# St_Olavs_Alarm.net
KiCad netlist of a schematic drawn in Altium Designer
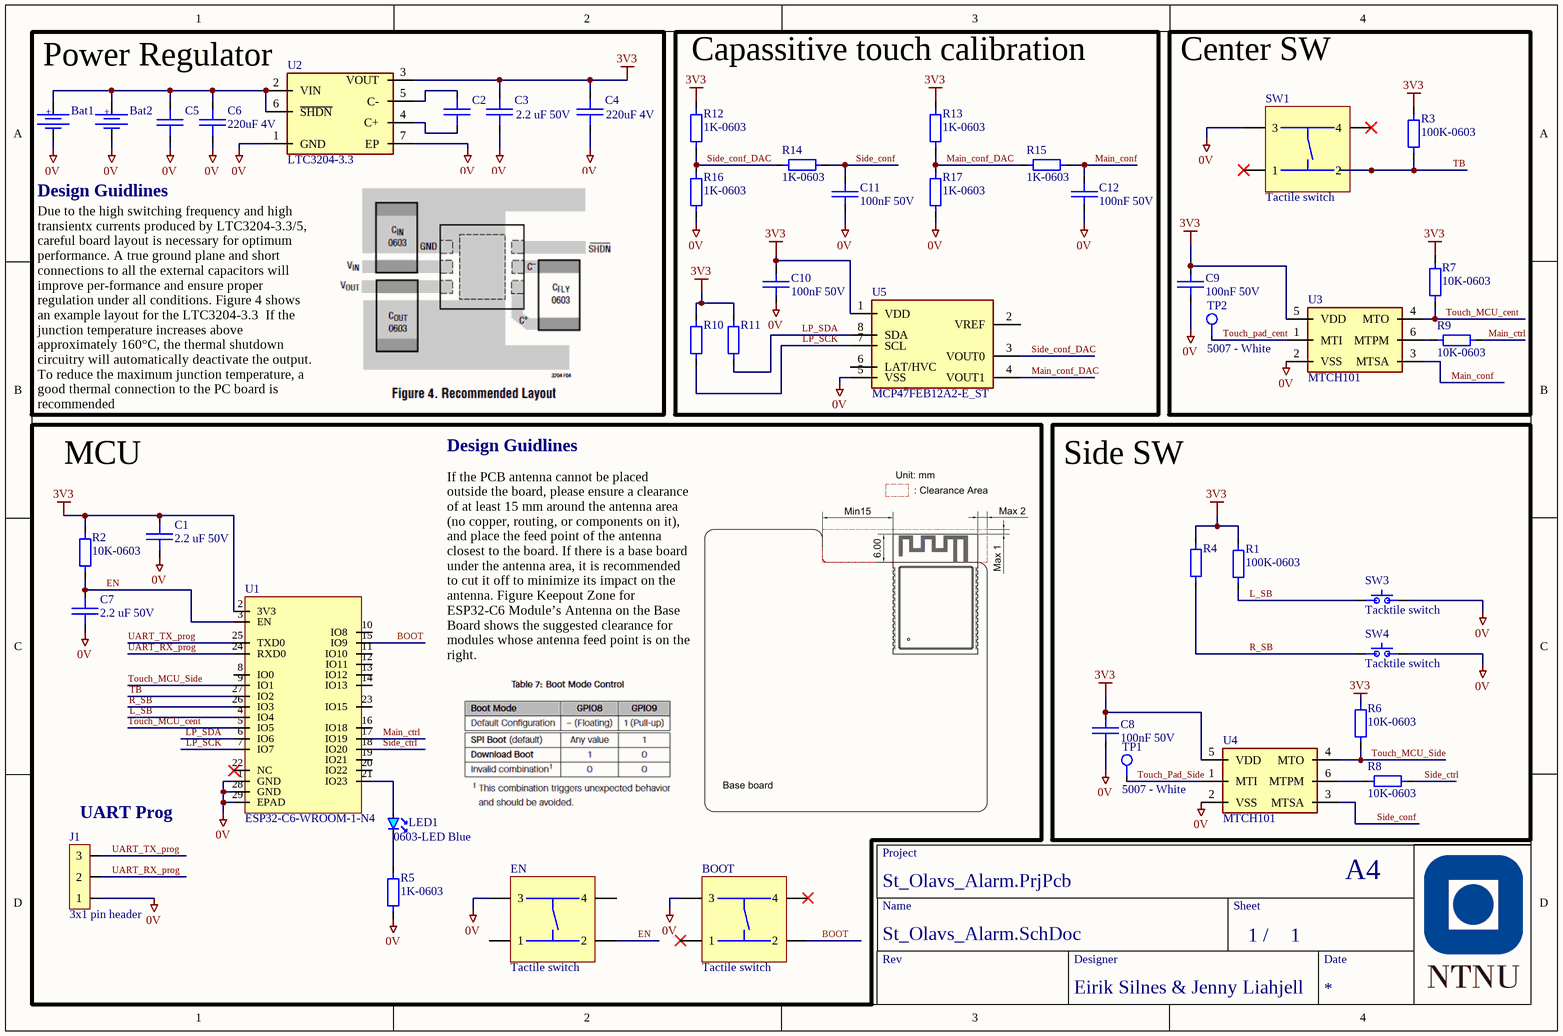
[diagram p0: St_Olavs_Alarm.SchDoc]

(export (version "E")
  (design (tool "Eeschema 10.0.6"))
  (components
    (comp (ref "Bat1")
      (value "Bat Holder L-KLS5-CR2032-23-B1")
      (footprint "St_Olavs_alarm:L-KLS5-CR2032-23-B1")
      (description "Bat Holder CR2032 SMD")
      (fields
        (field (name "MANUFACTURER") "KLS Electronic")
        (field (name "MANUFACTURER PART NUMBER") "L-KLS5-CR2032-23-B1")
        (field (name "AUTHOR") "rsk")
      )
      (libsource (lib "St_Olavs_alarm") (part "CMP-023-000003.0.1"))
    )
    (comp (ref "Bat2")
      (value "Bat Holder L-KLS5-CR2032-23-B1")
      (footprint "St_Olavs_alarm:L-KLS5-CR2032-23-B1")
      (description "Bat Holder CR2032 SMD")
      (fields
        (field (name "MANUFACTURER") "KLS Electronic")
        (field (name "MANUFACTURER PART NUMBER") "L-KLS5-CR2032-23-B1")
        (field (name "AUTHOR") "rsk")
      )
      (libsource (lib "St_Olavs_alarm") (part "CMP-023-000003.0.1"))
    )
    (comp (ref "BOOT")
      (value "Tactile switch")
      (footprint "St_Olavs_alarm:TE connectivity part no. 2-1437565-8")
      (description "Tactile switch SMD Mount")
      (libsource (lib "St_Olavs_alarm") (part "Tactile switch SMD"))
    )
    (comp (ref "C1")
      (value "2.2 uF 50V")
      (footprint "St_Olavs_alarm:0603 Capacitor")
      (description "2.2uF 10V 0603")
      (libsource (lib "St_Olavs_alarm") (part "CAP 2.2uF"))
    )
    (comp (ref "C2")
      (value "2.2 uF 50V")
      (footprint "St_Olavs_alarm:0603 Capacitor")
      (description "2.2uF 10V 0603")
      (libsource (lib "St_Olavs_alarm") (part "CAP 2.2uF"))
    )
    (comp (ref "C3")
      (value "2.2 uF 50V")
      (footprint "St_Olavs_alarm:0603 Capacitor")
      (description "2.2uF 10V 0603")
      (libsource (lib "St_Olavs_alarm") (part "CAP 2.2uF"))
    )
    (comp (ref "C4")
      (value "220uF 4V")
      (footprint "St_Olavs_alarm:1206 CAPC3216X190N")
      (description "220uF 4V 1206")
      (libsource (lib "St_Olavs_alarm") (part "CAP 220uF"))
    )
    (comp (ref "C5")
      (value "220uF 4V")
      (footprint "St_Olavs_alarm:1206 CAPC3216X190N")
      (description "220uF 4V 1206")
      (libsource (lib "St_Olavs_alarm") (part "CAP 220uF"))
    )
    (comp (ref "C6")
      (value "220uF 4V")
      (footprint "St_Olavs_alarm:1206 CAPC3216X190N")
      (description "220uF 4V 1206")
      (libsource (lib "St_Olavs_alarm") (part "CAP 220uF"))
    )
    (comp (ref "C7")
      (value "2.2 uF 50V")
      (footprint "St_Olavs_alarm:0603 Capacitor")
      (description "2.2uF 10V 0603")
      (libsource (lib "St_Olavs_alarm") (part "CAP 2.2uF"))
    )
    (comp (ref "C8")
      (value "100nF 50V")
      (footprint "St_Olavs_alarm:0603 Capacitor")
      (description "100nF 50V 0603")
      (libsource (lib "St_Olavs_alarm") (part "CAP 100nF"))
    )
    (comp (ref "C9")
      (value "100nF 50V")
      (footprint "St_Olavs_alarm:0603 Capacitor")
      (description "100nF 50V 0603")
      (libsource (lib "St_Olavs_alarm") (part "CAP 100nF"))
    )
    (comp (ref "C10")
      (value "100nF 50V")
      (footprint "St_Olavs_alarm:0603 Capacitor")
      (description "100nF 50V 0603")
      (libsource (lib "St_Olavs_alarm") (part "CAP 100nF"))
    )
    (comp (ref "C11")
      (value "100nF 50V")
      (footprint "St_Olavs_alarm:0603 Capacitor")
      (description "100nF 50V 0603")
      (libsource (lib "St_Olavs_alarm") (part "CAP 100nF"))
    )
    (comp (ref "C12")
      (value "100nF 50V")
      (footprint "St_Olavs_alarm:0603 Capacitor")
      (description "100nF 50V 0603")
      (libsource (lib "St_Olavs_alarm") (part "CAP 100nF"))
    )
    (comp (ref "EN")
      (value "Tactile switch")
      (footprint "St_Olavs_alarm:TE connectivity part no. 2-1437565-8")
      (description "Tactile switch SMD Mount")
      (libsource (lib "St_Olavs_alarm") (part "Tactile switch SMD"))
    )
    (comp (ref "J1")
      (value "3x1 pin header")
      (footprint "St_Olavs_alarm:Pin Header 1x3 TH Pitch 2.54mm")
      (description "2.54mm pitch")
      (libsource (lib "St_Olavs_alarm") (part "CMP-001-A02-7"))
    )
    (comp (ref "LED1")
      (value "0603-LED Blue")
      (footprint "St_Olavs_alarm:0603-Diode LED, Blue")
      (libsource (lib "St_Olavs_alarm") (part "0603-LED Blue"))
    )
    (comp (ref "R1")
      (value "100K-0603")
      (footprint "St_Olavs_alarm:0603 RESISTOR")
      (description "Res 100K Ohm Thick Film 0603 1% 1/10W ±100ppm/°C Molded SMD SMD Paper T/R")
      (libsource (lib "St_Olavs_alarm") (part "CMP-009-00186-5_1"))
    )
    (comp (ref "R2")
      (value "10K-0603")
      (footprint "St_Olavs_alarm:0603 RESISTOR")
      (description "Res 10K Ohm Thick Film 0603 1% 1/10W ±100ppm/°C Molded SMD SMD Paper T/R")
      (libsource (lib "St_Olavs_alarm") (part "CMP-009-00186-5"))
    )
    (comp (ref "R3")
      (value "100K-0603")
      (footprint "St_Olavs_alarm:0603 RESISTOR")
      (description "Res 100K Ohm Thick Film 0603 1% 1/10W ±100ppm/°C Molded SMD SMD Paper T/R")
      (libsource (lib "St_Olavs_alarm") (part "CMP-009-00186-5_1"))
    )
    (comp (ref "R4")
      (value "100K-0603")
      (footprint "St_Olavs_alarm:0603 RESISTOR")
      (description "Res 100K Ohm Thick Film 0603 1% 1/10W ±100ppm/°C Molded SMD SMD Paper T/R")
      (libsource (lib "St_Olavs_alarm") (part "CMP-009-00186-5_1"))
    )
    (comp (ref "R5")
      (value "1K-0603")
      (footprint "St_Olavs_alarm:0603 RESISTOR")
      (description "Res 1K Ohm Thick Film 0603 1% 1/10W ±100ppm/°C Molded SMD SMD Paper T/R")
      (libsource (lib "St_Olavs_alarm") (part "CMP-009-00186-5_1_1"))
    )
    (comp (ref "R6")
      (value "10K-0603")
      (footprint "St_Olavs_alarm:0603 RESISTOR")
      (description "Res 10K Ohm Thick Film 0603 1% 1/10W ±100ppm/°C Molded SMD SMD Paper T/R")
      (libsource (lib "St_Olavs_alarm") (part "CMP-009-00186-5"))
    )
    (comp (ref "R7")
      (value "10K-0603")
      (footprint "St_Olavs_alarm:0603 RESISTOR")
      (description "Res 10K Ohm Thick Film 0603 1% 1/10W ±100ppm/°C Molded SMD SMD Paper T/R")
      (libsource (lib "St_Olavs_alarm") (part "CMP-009-00186-5"))
    )
    (comp (ref "R8")
      (value "10K-0603")
      (footprint "St_Olavs_alarm:0603 RESISTOR")
      (description "Res 10K Ohm Thick Film 0603 1% 1/10W ±100ppm/°C Molded SMD SMD Paper T/R")
      (libsource (lib "St_Olavs_alarm") (part "CMP-009-00186-5"))
    )
    (comp (ref "R9")
      (value "10K-0603")
      (footprint "St_Olavs_alarm:0603 RESISTOR")
      (description "Res 10K Ohm Thick Film 0603 1% 1/10W ±100ppm/°C Molded SMD SMD Paper T/R")
      (libsource (lib "St_Olavs_alarm") (part "CMP-009-00186-5"))
    )
    (comp (ref "R10")
      (value "10K-0603")
      (footprint "St_Olavs_alarm:0603 RESISTOR")
      (description "Res 10K Ohm Thick Film 0603 1% 1/10W ±100ppm/°C Molded SMD SMD Paper T/R")
      (libsource (lib "St_Olavs_alarm") (part "CMP-009-00186-5"))
    )
    (comp (ref "R11")
      (value "10K-0603")
      (footprint "St_Olavs_alarm:0603 RESISTOR")
      (description "Res 10K Ohm Thick Film 0603 1% 1/10W ±100ppm/°C Molded SMD SMD Paper T/R")
      (libsource (lib "St_Olavs_alarm") (part "CMP-009-00186-5"))
    )
    (comp (ref "R12")
      (value "1K-0603")
      (footprint "St_Olavs_alarm:0603 RESISTOR")
      (description "Res 1K Ohm Thick Film 0603 1% 1/10W ±100ppm/°C Molded SMD SMD Paper T/R")
      (libsource (lib "St_Olavs_alarm") (part "CMP-009-00186-5_1_1"))
    )
    (comp (ref "R13")
      (value "1K-0603")
      (footprint "St_Olavs_alarm:0603 RESISTOR")
      (description "Res 1K Ohm Thick Film 0603 1% 1/10W ±100ppm/°C Molded SMD SMD Paper T/R")
      (libsource (lib "St_Olavs_alarm") (part "CMP-009-00186-5_1_1"))
    )
    (comp (ref "R14")
      (value "1K-0603")
      (footprint "St_Olavs_alarm:0603 RESISTOR")
      (description "Res 1K Ohm Thick Film 0603 1% 1/10W ±100ppm/°C Molded SMD SMD Paper T/R")
      (libsource (lib "St_Olavs_alarm") (part "CMP-009-00186-5_1_1"))
    )
    (comp (ref "R15")
      (value "1K-0603")
      (footprint "St_Olavs_alarm:0603 RESISTOR")
      (description "Res 1K Ohm Thick Film 0603 1% 1/10W ±100ppm/°C Molded SMD SMD Paper T/R")
      (libsource (lib "St_Olavs_alarm") (part "CMP-009-00186-5_1_1"))
    )
    (comp (ref "R16")
      (value "1K-0603")
      (footprint "St_Olavs_alarm:0603 RESISTOR")
      (description "Res 1K Ohm Thick Film 0603 1% 1/10W ±100ppm/°C Molded SMD SMD Paper T/R")
      (libsource (lib "St_Olavs_alarm") (part "CMP-009-00186-5_1_1"))
    )
    (comp (ref "R17")
      (value "1K-0603")
      (footprint "St_Olavs_alarm:0603 RESISTOR")
      (description "Res 1K Ohm Thick Film 0603 1% 1/10W ±100ppm/°C Molded SMD SMD Paper T/R")
      (libsource (lib "St_Olavs_alarm") (part "CMP-009-00186-5_1_1"))
    )
    (comp (ref "SW1")
      (value "Tactile switch")
      (footprint "St_Olavs_alarm:430182080816")
      (description "Tactile switch SMD Longer Neck")
      (libsource (lib "St_Olavs_alarm") (part "Tactile switch Big"))
    )
    (comp (ref "SW3")
      (value "Tacktile switch")
      (footprint "St_Olavs_alarm:KSS241GLFS")
      (description "KSS241GLFS")
      (libsource (lib "St_Olavs_alarm") (part "KSS241GLFS"))
    )
    (comp (ref "SW4")
      (value "Tacktile switch")
      (footprint "St_Olavs_alarm:KSS241GLFS")
      (description "KSS241GLFS")
      (libsource (lib "St_Olavs_alarm") (part "KSS241GLFS"))
    )
    (comp (ref "TP1")
      (value "5007 - White")
      (footprint "St_Olavs_alarm:5006-Footprint-1")
      (description "KEYSTONE - 5007 - TEST POINT, THT, WHITE")
      (libsource (lib "St_Olavs_alarm") (part "CMP-00049-A.2"))
    )
    (comp (ref "TP2")
      (value "5007 - White")
      (footprint "St_Olavs_alarm:5006-Footprint-1")
      (description "KEYSTONE - 5007 - TEST POINT, THT, WHITE")
      (libsource (lib "St_Olavs_alarm") (part "CMP-00049-A.2"))
    )
    (comp (ref "U1")
      (value "ESP32-C6-WROOM-1-N4")
      (footprint "St_Olavs_alarm:ESP32-C6-WROOM-1-N4-Footprint-1")
      (libsource (lib "St_Olavs_alarm") (part "CMP-020-00028-2"))
    )
    (comp (ref "U2")
      (value "LTC3204-3.3")
      (footprint "St_Olavs_alarm:LTC3204")
      (libsource (lib "St_Olavs_alarm") (part "LTC3204-3.3"))
    )
    (comp (ref "U3")
      (value "MTCH101")
      (footprint "St_Olavs_alarm:SOT95P270X145-6N")
      (description "Capasitive touch sensor")
      (fields
        (field (name "MANUFACTURER_PART_NUMBER") "MTCH101-I/OT")
        (field (name "MOUSER PART NUMBER") "579-MTCH101-I/OT")
      )
      (libsource (lib "St_Olavs_alarm") (part "MTCH101-I_OT"))
    )
    (comp (ref "U4")
      (value "MTCH101")
      (footprint "St_Olavs_alarm:SOT95P270X145-6N")
      (description "Capasitive touch sensor")
      (fields
        (field (name "MANUFACTURER_PART_NUMBER") "MTCH101-I/OT")
        (field (name "MOUSER PART NUMBER") "579-MTCH101-I/OT")
      )
      (libsource (lib "St_Olavs_alarm") (part "MTCH101-I_OT"))
    )
    (comp (ref "U5")
      (value "MCP47FEB12A2-E_ST")
      (footprint "St_Olavs_alarm:SOP65P640X120-8N")
      (description "Integrated Circuit")
      (fields
        (field (name "MANUFACTURER_PART_NUMBER") "MCP47FEB12A2-E/ST")
        (field (name "MOUSER PART NUMBER") "579-MCP47FEB12A2EST")
      )
      (libsource (lib "St_Olavs_alarm") (part "MCP47FEB12A2-E_ST"))
    )
  )
  (nets
    (net (code "1") (name "/BOOT") (class "Default")
      (node (ref "BOOT") (pin "2") (pinfunction "2_2") (pintype "passive"))
      (node (ref "U1") (pin "15") (pinfunction "IO9_15") (pintype "passive"))
    )
    (net (code "2") (name "/EN") (class "Default")
      (node (ref "C7") (pin "2") (pinfunction "2_2") (pintype "passive"))
      (node (ref "EN") (pin "2") (pinfunction "2_2") (pintype "passive"))
      (node (ref "R2") (pin "1") (pinfunction "1_1") (pintype "passive"))
      (node (ref "U1") (pin "3") (pinfunction "EN_3") (pintype "passive"))
    )
    (net (code "3") (name "/LP_SCK") (class "Default")
      (node (ref "R10") (pin "1") (pinfunction "1_1") (pintype "passive"))
      (node (ref "U1") (pin "7") (pinfunction "IO7_7") (pintype "passive"))
      (node (ref "U5") (pin "7") (pinfunction "SCL_7") (pintype "passive"))
    )
    (net (code "4") (name "/LP_SDA") (class "Default")
      (node (ref "R11") (pin "1") (pinfunction "1_1") (pintype "passive"))
      (node (ref "U1") (pin "6") (pinfunction "IO6_6") (pintype "passive"))
      (node (ref "U5") (pin "8") (pinfunction "SDA_8") (pintype "passive"))
    )
    (net (code "5") (name "/L_SB") (class "Default")
      (node (ref "R1") (pin "1") (pinfunction "1_1") (pintype "passive"))
      (node (ref "SW3") (pin "1") (pinfunction "1_1") (pintype "passive"))
      (node (ref "U1") (pin "4") (pinfunction "IO4_4") (pintype "passive"))
    )
    (net (code "6") (name "/Main_conf") (class "Default")
      (node (ref "C12") (pin "1") (pinfunction "1_1") (pintype "passive"))
      (node (ref "R15") (pin "1") (pinfunction "1_1") (pintype "passive"))
      (node (ref "U3") (pin "3") (pinfunction "MTSA_3") (pintype "passive"))
    )
    (net (code "7") (name "/Main_conf_DAC") (class "Default")
      (node (ref "R13") (pin "2") (pinfunction "1_2") (pintype "passive"))
      (node (ref "R15") (pin "2") (pinfunction "1_2") (pintype "passive"))
      (node (ref "R17") (pin "1") (pinfunction "1_1") (pintype "passive"))
      (node (ref "U5") (pin "4") (pinfunction "VOUT1_4") (pintype "passive"))
    )
    (net (code "8") (name "/Main_ctrl") (class "Default")
      (node (ref "R9") (pin "1") (pinfunction "1_1") (pintype "passive"))
      (node (ref "U1") (pin "17") (pinfunction "IO19_17") (pintype "passive"))
    )
    (net (code "9") (name "/R_SB") (class "Default")
      (node (ref "R4") (pin "1") (pinfunction "1_1") (pintype "passive"))
      (node (ref "SW4") (pin "1") (pinfunction "1_1") (pintype "passive"))
      (node (ref "U1") (pin "26") (pinfunction "IO3_26") (pintype "passive"))
    )
    (net (code "10") (name "/Side_conf") (class "Default")
      (node (ref "C11") (pin "1") (pinfunction "1_1") (pintype "passive"))
      (node (ref "R14") (pin "2") (pinfunction "1_2") (pintype "passive"))
      (node (ref "U4") (pin "3") (pinfunction "MTSA_3") (pintype "passive"))
    )
    (net (code "11") (name "/Side_conf_DAC") (class "Default")
      (node (ref "R12") (pin "1") (pinfunction "1_1") (pintype "passive"))
      (node (ref "R14") (pin "1") (pinfunction "1_1") (pintype "passive"))
      (node (ref "R16") (pin "2") (pinfunction "1_2") (pintype "passive"))
      (node (ref "U5") (pin "3") (pinfunction "VOUT0_3") (pintype "passive"))
    )
    (net (code "12") (name "/Side_ctrl") (class "Default")
      (node (ref "R8") (pin "2") (pinfunction "1_2") (pintype "passive"))
      (node (ref "U1") (pin "18") (pinfunction "IO20_18") (pintype "passive"))
    )
    (net (code "13") (name "/TB") (class "Default")
      (node (ref "R3") (pin "1") (pinfunction "1_1") (pintype "passive"))
      (node (ref "SW1") (pin "2") (pinfunction "2_2") (pintype "passive"))
      (node (ref "U1") (pin "27") (pinfunction "IO2_27") (pintype "passive"))
    )
    (net (code "14") (name "/Touch_MCU_Side") (class "Default")
      (node (ref "R6") (pin "1") (pinfunction "1_1") (pintype "passive"))
      (node (ref "U1") (pin "9") (pinfunction "IO1_9") (pintype "passive"))
      (node (ref "U4") (pin "4") (pinfunction "MTO_4") (pintype "passive"))
    )
    (net (code "15") (name "/Touch_MCU_cent") (class "Default")
      (node (ref "R7") (pin "1") (pinfunction "1_1") (pintype "passive"))
      (node (ref "U1") (pin "5") (pinfunction "IO5_5") (pintype "passive"))
      (node (ref "U3") (pin "4") (pinfunction "MTO_4") (pintype "passive"))
    )
    (net (code "16") (name "/Touch_Pad_Side") (class "Default")
      (node (ref "TP1") (pin "1") (pinfunction "1_1") (pintype "passive"))
      (node (ref "U4") (pin "1") (pinfunction "MTI_1") (pintype "passive"))
    )
    (net (code "17") (name "/Touch_pad_cent") (class "Default")
      (node (ref "TP2") (pin "1") (pinfunction "1_1") (pintype "passive"))
      (node (ref "U3") (pin "1") (pinfunction "MTI_1") (pintype "passive"))
    )
    (net (code "18") (name "/UART_RX_prog") (class "Default")
      (node (ref "J1") (pin "2") (pinfunction "2_2") (pintype "passive"))
      (node (ref "U1") (pin "24") (pinfunction "RXD0_24") (pintype "passive"))
    )
    (net (code "19") (name "/UART_TX_prog") (class "Default")
      (node (ref "J1") (pin "3") (pinfunction "3_3") (pintype "passive"))
      (node (ref "U1") (pin "25") (pinfunction "TXD0_25") (pintype "passive"))
    )
    (net (code "20") (name "0V") (class "Default")
      (node (ref "BOOT") (pin "3") (pinfunction "3_3") (pintype "passive"))
      (node (ref "Bat1") (pin "2") (pintype "passive"))
      (node (ref "Bat2") (pin "2") (pintype "passive"))
      (node (ref "C1") (pin "1") (pinfunction "1_1") (pintype "passive"))
      (node (ref "C10") (pin "2") (pinfunction "2_2") (pintype "passive"))
      (node (ref "C11") (pin "2") (pinfunction "2_2") (pintype "passive"))
      (node (ref "C12") (pin "2") (pinfunction "2_2") (pintype "passive"))
      (node (ref "C3") (pin "1") (pinfunction "1_1") (pintype "passive"))
      (node (ref "C4") (pin "2") (pinfunction "2_2") (pintype "passive"))
      (node (ref "C5") (pin "2") (pinfunction "2_2") (pintype "passive"))
      (node (ref "C6") (pin "2") (pinfunction "2_2") (pintype "passive"))
      (node (ref "C7") (pin "1") (pinfunction "1_1") (pintype "passive"))
      (node (ref "C8") (pin "2") (pinfunction "2_2") (pintype "passive"))
      (node (ref "C9") (pin "2") (pinfunction "2_2") (pintype "passive"))
      (node (ref "EN") (pin "3") (pinfunction "3_3") (pintype "passive"))
      (node (ref "J1") (pin "1") (pinfunction "1_1") (pintype "passive"))
      (node (ref "R16") (pin "1") (pinfunction "1_1") (pintype "passive"))
      (node (ref "R17") (pin "2") (pinfunction "1_2") (pintype "passive"))
      (node (ref "R5") (pin "1") (pinfunction "1_1") (pintype "passive"))
      (node (ref "SW1") (pin "3") (pinfunction "3_3") (pintype "passive"))
      (node (ref "SW3") (pin "2") (pinfunction "2_2") (pintype "passive"))
      (node (ref "SW4") (pin "2") (pinfunction "2_2") (pintype "passive"))
      (node (ref "U1") (pin "1") (pinfunction "GND_1") (pintype "passive"))
      (node (ref "U1") (pin "28") (pinfunction "GND_28") (pintype "power_in"))
      (node (ref "U1") (pin "29") (pinfunction "EPAD_29") (pintype "power_in"))
      (node (ref "U2") (pin "1") (pinfunction "GND_1") (pintype "passive"))
      (node (ref "U2") (pin "7") (pinfunction "EP_7") (pintype "passive"))
      (node (ref "U3") (pin "2") (pinfunction "VSS_2") (pintype "passive"))
      (node (ref "U4") (pin "2") (pinfunction "VSS_2") (pintype "passive"))
      (node (ref "U5") (pin "5") (pinfunction "VSS_5") (pintype "passive"))
    )
    (net (code "21") (name "3V3") (class "Default")
      (node (ref "C1") (pin "2") (pinfunction "2_2") (pintype "passive"))
      (node (ref "C10") (pin "1") (pinfunction "1_1") (pintype "passive"))
      (node (ref "C3") (pin "2") (pinfunction "2_2") (pintype "passive"))
      (node (ref "C4") (pin "1") (pinfunction "1_1") (pintype "passive"))
      (node (ref "C8") (pin "1") (pinfunction "1_1") (pintype "passive"))
      (node (ref "C9") (pin "1") (pinfunction "1_1") (pintype "passive"))
      (node (ref "R1") (pin "2") (pinfunction "1_2") (pintype "passive"))
      (node (ref "R10") (pin "2") (pinfunction "1_2") (pintype "passive"))
      (node (ref "R11") (pin "2") (pinfunction "1_2") (pintype "passive"))
      (node (ref "R12") (pin "2") (pinfunction "1_2") (pintype "passive"))
      (node (ref "R13") (pin "1") (pinfunction "1_1") (pintype "passive"))
      (node (ref "R2") (pin "2") (pinfunction "1_2") (pintype "passive"))
      (node (ref "R3") (pin "2") (pinfunction "1_2") (pintype "passive"))
      (node (ref "R4") (pin "2") (pinfunction "1_2") (pintype "passive"))
      (node (ref "R6") (pin "2") (pinfunction "1_2") (pintype "passive"))
      (node (ref "R7") (pin "2") (pinfunction "1_2") (pintype "passive"))
      (node (ref "U1") (pin "2") (pinfunction "3V3_2") (pintype "passive"))
      (node (ref "U2") (pin "3") (pinfunction "VOUT_3") (pintype "passive"))
      (node (ref "U3") (pin "5") (pinfunction "VDD_5") (pintype "passive"))
      (node (ref "U4") (pin "5") (pinfunction "VDD_5") (pintype "passive"))
      (node (ref "U5") (pin "1") (pinfunction "VDD_1") (pintype "passive"))
    )
    (net (code "22") (name "Net-(LED1-A)") (class "Default")
      (node (ref "LED1") (pin "1") (pinfunction "A_1") (pintype "passive"))
      (node (ref "U1") (pin "21") (pinfunction "IO23_21") (pintype "passive"))
    )
    (net (code "23") (name "Net-(LED1-K)") (class "Default")
      (node (ref "LED1") (pin "2") (pinfunction "K_2") (pintype "passive"))
      (node (ref "R5") (pin "2") (pinfunction "1_2") (pintype "passive"))
    )
    (net (code "24") (name "Net-(U2-C+)") (class "Default")
      (node (ref "C2") (pin "1") (pinfunction "1_1") (pintype "passive"))
      (node (ref "U2") (pin "4") (pinfunction "C+_4") (pintype "passive"))
    )
    (net (code "25") (name "Net-(U2-C-)") (class "Default")
      (node (ref "C2") (pin "2") (pinfunction "2_2") (pintype "passive"))
      (node (ref "U2") (pin "5") (pinfunction "C-_5") (pintype "passive"))
    )
    (net (code "26") (name "Net-(U2-VIN)") (class "Default")
      (node (ref "Bat1") (pin "1") (pintype "passive"))
      (node (ref "Bat2") (pin "1") (pintype "passive"))
      (node (ref "C5") (pin "1") (pinfunction "1_1") (pintype "passive"))
      (node (ref "C6") (pin "1") (pinfunction "1_1") (pintype "passive"))
      (node (ref "U2") (pin "2") (pinfunction "VIN_2") (pintype "passive"))
      (node (ref "U2") (pin "6") (pinfunction "~{SHDN}_6") (pintype "passive"))
    )
    (net (code "27") (name "Net-(U3-MTPM)") (class "Default")
      (node (ref "R9") (pin "2") (pinfunction "1_2") (pintype "passive"))
      (node (ref "U3") (pin "6") (pinfunction "MTPM_6") (pintype "passive"))
    )
    (net (code "28") (name "Net-(U4-MTPM)") (class "Default")
      (node (ref "R8") (pin "1") (pinfunction "1_1") (pintype "passive"))
      (node (ref "U4") (pin "6") (pinfunction "MTPM_6") (pintype "passive"))
    )
    (net (code "29") (name "unconnected-(BOOT-Pad1)") (class "Default")
      (node (ref "BOOT") (pin "1") (pinfunction "1_1") (pintype "passive+no_connect"))
    )
    (net (code "30") (name "unconnected-(BOOT-Pad4)") (class "Default")
      (node (ref "BOOT") (pin "4") (pinfunction "4_4") (pintype "passive+no_connect"))
    )
    (net (code "31") (name "unconnected-(EN-Pad1)") (class "Default")
      (node (ref "EN") (pin "1") (pinfunction "1_1") (pintype "passive"))
    )
    (net (code "32") (name "unconnected-(EN-Pad4)") (class "Default")
      (node (ref "EN") (pin "4") (pinfunction "4_4") (pintype "passive"))
    )
    (net (code "33") (name "unconnected-(SW1-Pad1)") (class "Default")
      (node (ref "SW1") (pin "1") (pinfunction "1_1") (pintype "passive+no_connect"))
    )
    (net (code "34") (name "unconnected-(SW1-Pad4)") (class "Default")
      (node (ref "SW1") (pin "4") (pinfunction "4_4") (pintype "passive+no_connect"))
    )
    (net (code "35") (name "unconnected-(U1-IO0-Pad8)") (class "Default")
      (node (ref "U1") (pin "8") (pinfunction "IO0_8") (pintype "passive"))
    )
    (net (code "36") (name "unconnected-(U1-IO8-Pad10)") (class "Default")
      (node (ref "U1") (pin "10") (pinfunction "IO8_10") (pintype "passive"))
    )
    (net (code "37") (name "unconnected-(U1-IO10-Pad11)") (class "Default")
      (node (ref "U1") (pin "11") (pinfunction "IO10_11") (pintype "passive"))
    )
    (net (code "38") (name "unconnected-(U1-IO11-Pad12)") (class "Default")
      (node (ref "U1") (pin "12") (pinfunction "IO11_12") (pintype "passive"))
    )
    (net (code "39") (name "unconnected-(U1-IO12-Pad13)") (class "Default")
      (node (ref "U1") (pin "13") (pinfunction "IO12_13") (pintype "passive"))
    )
    (net (code "40") (name "unconnected-(U1-IO13-Pad14)") (class "Default")
      (node (ref "U1") (pin "14") (pinfunction "IO13_14") (pintype "passive"))
    )
    (net (code "41") (name "unconnected-(U1-IO15-Pad23)") (class "Default")
      (node (ref "U1") (pin "23") (pinfunction "IO15_23") (pintype "passive"))
    )
    (net (code "42") (name "unconnected-(U1-IO18-Pad16)") (class "Default")
      (node (ref "U1") (pin "16") (pinfunction "IO18_16") (pintype "passive"))
    )
    (net (code "43") (name "unconnected-(U1-IO21-Pad19)") (class "Default")
      (node (ref "U1") (pin "19") (pinfunction "IO21_19") (pintype "passive"))
    )
    (net (code "44") (name "unconnected-(U1-IO22-Pad20)") (class "Default")
      (node (ref "U1") (pin "20") (pinfunction "IO22_20") (pintype "passive"))
    )
    (net (code "45") (name "unconnected-(U1-NC-Pad22)") (class "Default")
      (node (ref "U1") (pin "22") (pinfunction "NC_22") (pintype "passive+no_connect"))
    )
    (net (code "46") (name "unconnected-(U5-LAT{slash}HVC-Pad6)") (class "Default")
      (node (ref "U5") (pin "6") (pinfunction "LAT/HVC_6") (pintype "passive"))
    )
    (net (code "47") (name "unconnected-(U5-VREF-Pad2)") (class "Default")
      (node (ref "U5") (pin "2") (pinfunction "VREF_2") (pintype "passive"))
    )
  )
)
